# POWER_B3.net
KiCad netlist of a schematic drawn in Altium Designer
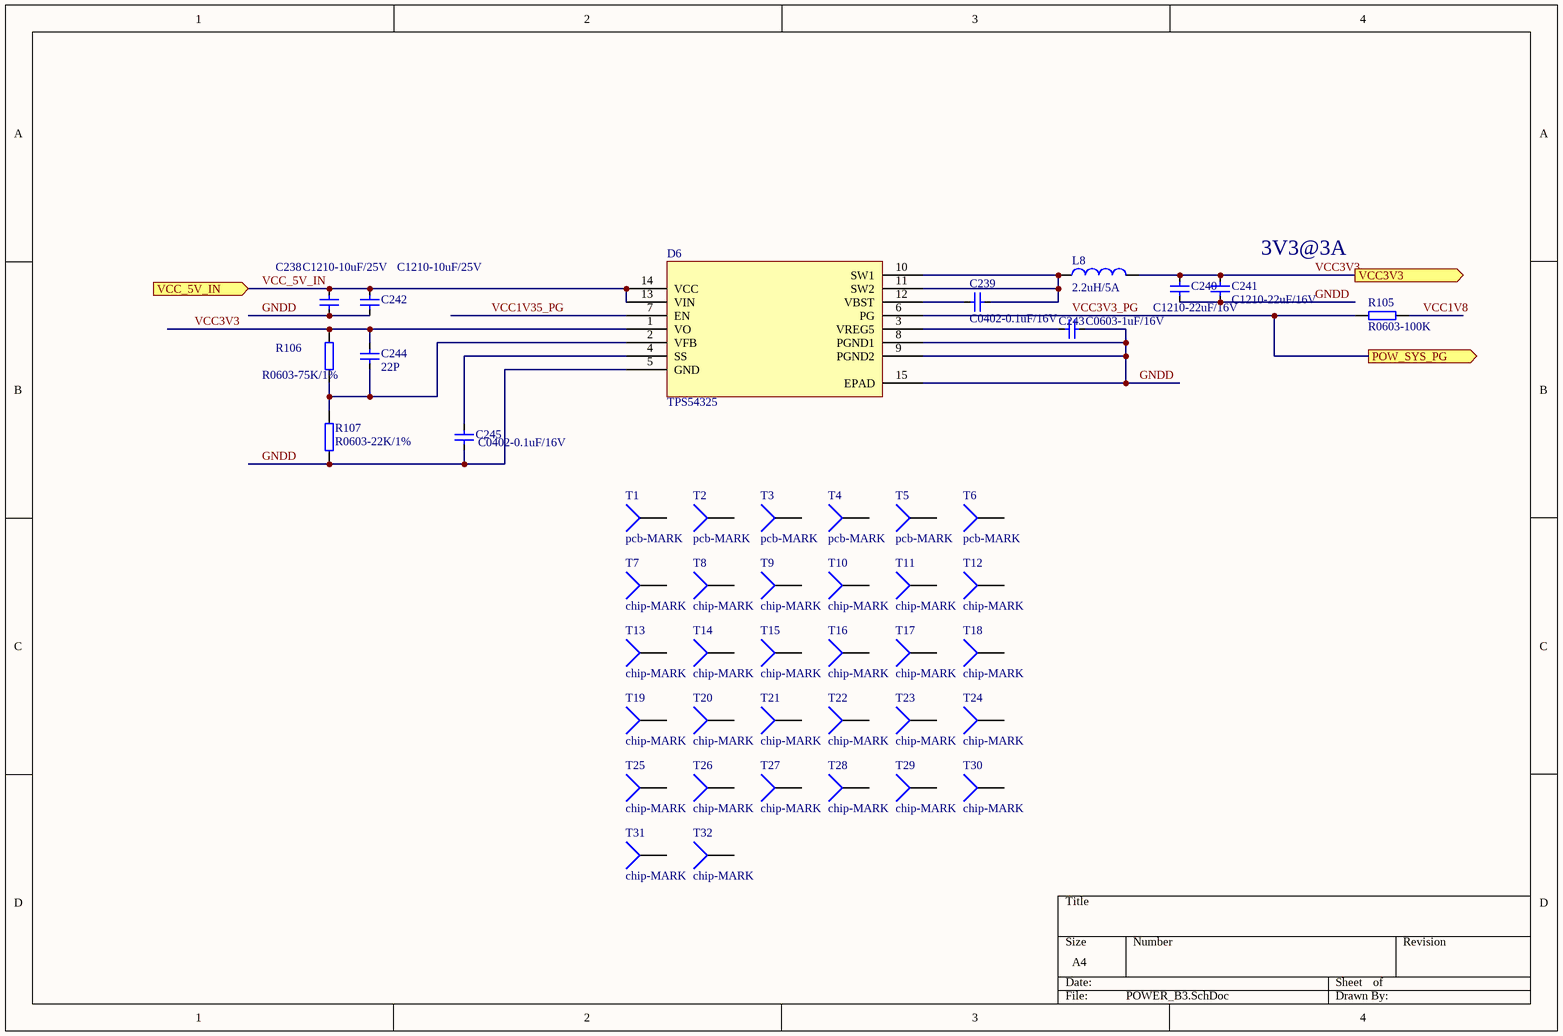
[diagram p0: POWER_B3.SchDoc]

(export (version "E")
  (design (tool "Eeschema 10.0.6"))
  (components
    (comp (ref "C238")
      (value "C1210-10uF/25V")
      (footprint "C1210")
      (fields (field (name "SCHEMATIC_PART") "CAP"))
      (libsource (lib "Database_Libs1") (part "CAP"))
    )
    (comp (ref "C239")
      (value "C0402-0.1uF/16V")
      (footprint "C0402")
      (description "X7R")
      (fields (field (name "SCHEMATIC_PART") "CAP") (field (name "MANUFACTURER") "SAMSUNG"))
      (libsource (lib "Database_Libs1") (part "CAP"))
    )
    (comp (ref "C240")
      (value "C1210-22uF/16V")
      (footprint "C1210")
      (fields (field (name "SCHEMATIC_PART") "CAP"))
      (libsource (lib "Database_Libs1") (part "CAP"))
    )
    (comp (ref "C241")
      (value "C1210-22uF/16V")
      (footprint "C1210")
      (fields (field (name "SCHEMATIC_PART") "CAP"))
      (libsource (lib "Database_Libs1") (part "CAP"))
    )
    (comp (ref "C242")
      (value "C1210-10uF/25V")
      (footprint "C1210")
      (fields (field (name "SCHEMATIC_PART") "CAP"))
      (libsource (lib "Database_Libs1") (part "CAP"))
    )
    (comp (ref "C243")
      (value "C0603-1uF/16V")
      (footprint "C0603")
      (description "X7R")
      (fields (field (name "SCHEMATIC_PART") "CAP"))
      (libsource (lib "Database_Libs1") (part "CAP"))
    )
    (comp (ref "C244")
      (value "22P")
      (footprint "C0603")
      (description "X7R")
      (fields (field (name "SCHEMATIC_PART") "CAP"))
      (libsource (lib "Database_Libs1") (part "CAP"))
    )
    (comp (ref "C245")
      (value "C0402-0.1uF/16V")
      (footprint "C0402")
      (description "X7R")
      (fields (field (name "SCHEMATIC_PART") "CAP") (field (name "MANUFACTURER") "SAMSUNG"))
      (libsource (lib "Database_Libs1") (part "CAP"))
    )
    (comp (ref "D6") (value "TPS54325") (footprint "HTSSOP-14") (libsource (lib "SCHLIB1") (part "TPS54325")))
    (comp (ref "L8")
      (value "2.2uH/5A")
      (footprint "LSMD12-13X13")
      (fields (field (name "SCHEMATIC_PART") "INDUCTOR"))
      (libsource (lib "Database_Libs1") (part "INDUCTOR"))
    )
    (comp (ref "R105")
      (value "R0603-100K")
      (footprint "R0603")
      (fields (field (name "SCHEMATIC_PART") "RES") (field (name "MANUFACTURER") "HKT"))
      (libsource (lib "Database_Libs1") (part "RES"))
    )
    (comp (ref "R106")
      (value "R0603-75K/1%")
      (footprint "R0603")
      (fields (field (name "SCHEMATIC_PART") "RES") (field (name "MANUFACTURER") "HKT"))
      (libsource (lib "Database_Libs1") (part "RES"))
    )
    (comp (ref "R107")
      (value "R0603-22K/1%")
      (footprint "R0603")
      (fields (field (name "SCHEMATIC_PART") "RES") (field (name "MANUFACTURER") "HKT"))
      (libsource (lib "Database_Libs1") (part "RES"))
    )
    (comp (ref "T1")
      (value "pcb-MARK")
      (footprint "pcb-MARK")
      (description "PCB标示 MARK点")
      (libsource (lib "Database_Libs1") (part "pcb-MARK"))
    )
    (comp (ref "T2")
      (value "pcb-MARK")
      (footprint "pcb-MARK")
      (description "PCB标示 MARK点")
      (libsource (lib "Database_Libs1") (part "pcb-MARK"))
    )
    (comp (ref "T3")
      (value "pcb-MARK")
      (footprint "pcb-MARK")
      (description "PCB标示 MARK点")
      (libsource (lib "Database_Libs1") (part "pcb-MARK"))
    )
    (comp (ref "T4")
      (value "pcb-MARK")
      (footprint "pcb-MARK")
      (description "PCB标示 MARK点")
      (libsource (lib "Database_Libs1") (part "pcb-MARK"))
    )
    (comp (ref "T5")
      (value "pcb-MARK")
      (footprint "pcb-MARK")
      (description "PCB标示 MARK点")
      (libsource (lib "Database_Libs1") (part "pcb-MARK"))
    )
    (comp (ref "T6")
      (value "pcb-MARK")
      (footprint "pcb-MARK")
      (description "PCB标示 MARK点")
      (libsource (lib "Database_Libs1") (part "pcb-MARK"))
    )
    (comp (ref "T7")
      (value "chip-MARK")
      (footprint "chip-MARK")
      (description "芯片标示 MARK点")
      (libsource (lib "Database_Libs1") (part "chip-MARK"))
    )
    (comp (ref "T8")
      (value "chip-MARK")
      (footprint "chip-MARK")
      (description "芯片标示 MARK点")
      (libsource (lib "Database_Libs1") (part "chip-MARK"))
    )
    (comp (ref "T9")
      (value "chip-MARK")
      (footprint "chip-MARK")
      (description "芯片标示 MARK点")
      (libsource (lib "Database_Libs1") (part "chip-MARK"))
    )
    (comp (ref "T10")
      (value "chip-MARK")
      (footprint "chip-MARK")
      (description "芯片标示 MARK点")
      (libsource (lib "Database_Libs1") (part "chip-MARK"))
    )
    (comp (ref "T11")
      (value "chip-MARK")
      (footprint "chip-MARK")
      (description "芯片标示 MARK点")
      (libsource (lib "Database_Libs1") (part "chip-MARK"))
    )
    (comp (ref "T12")
      (value "chip-MARK")
      (footprint "chip-MARK")
      (description "芯片标示 MARK点")
      (libsource (lib "Database_Libs1") (part "chip-MARK"))
    )
    (comp (ref "T13")
      (value "chip-MARK")
      (footprint "chip-MARK")
      (description "芯片标示 MARK点")
      (libsource (lib "Database_Libs1") (part "chip-MARK"))
    )
    (comp (ref "T14")
      (value "chip-MARK")
      (footprint "chip-MARK")
      (description "芯片标示 MARK点")
      (libsource (lib "Database_Libs1") (part "chip-MARK"))
    )
    (comp (ref "T15")
      (value "chip-MARK")
      (footprint "chip-MARK")
      (description "芯片标示 MARK点")
      (libsource (lib "Database_Libs1") (part "chip-MARK"))
    )
    (comp (ref "T16")
      (value "chip-MARK")
      (footprint "chip-MARK")
      (description "芯片标示 MARK点")
      (libsource (lib "Database_Libs1") (part "chip-MARK"))
    )
    (comp (ref "T17")
      (value "chip-MARK")
      (footprint "chip-MARK")
      (description "芯片标示 MARK点")
      (libsource (lib "Database_Libs1") (part "chip-MARK"))
    )
    (comp (ref "T18")
      (value "chip-MARK")
      (footprint "chip-MARK")
      (description "芯片标示 MARK点")
      (libsource (lib "Database_Libs1") (part "chip-MARK"))
    )
    (comp (ref "T19")
      (value "chip-MARK")
      (footprint "chip-MARK")
      (description "芯片标示 MARK点")
      (libsource (lib "Database_Libs1") (part "chip-MARK"))
    )
    (comp (ref "T20")
      (value "chip-MARK")
      (footprint "chip-MARK")
      (description "芯片标示 MARK点")
      (libsource (lib "Database_Libs1") (part "chip-MARK"))
    )
    (comp (ref "T21")
      (value "chip-MARK")
      (footprint "chip-MARK")
      (description "芯片标示 MARK点")
      (libsource (lib "Database_Libs1") (part "chip-MARK"))
    )
    (comp (ref "T22")
      (value "chip-MARK")
      (footprint "chip-MARK")
      (description "芯片标示 MARK点")
      (libsource (lib "Database_Libs1") (part "chip-MARK"))
    )
    (comp (ref "T23")
      (value "chip-MARK")
      (footprint "chip-MARK")
      (description "芯片标示 MARK点")
      (libsource (lib "Database_Libs1") (part "chip-MARK"))
    )
    (comp (ref "T24")
      (value "chip-MARK")
      (footprint "chip-MARK")
      (description "芯片标示 MARK点")
      (libsource (lib "Database_Libs1") (part "chip-MARK"))
    )
    (comp (ref "T25")
      (value "chip-MARK")
      (footprint "chip-MARK")
      (description "芯片标示 MARK点")
      (libsource (lib "Database_Libs1") (part "chip-MARK"))
    )
    (comp (ref "T26")
      (value "chip-MARK")
      (footprint "chip-MARK")
      (description "芯片标示 MARK点")
      (libsource (lib "Database_Libs1") (part "chip-MARK"))
    )
    (comp (ref "T27")
      (value "chip-MARK")
      (footprint "chip-MARK")
      (description "芯片标示 MARK点")
      (libsource (lib "Database_Libs1") (part "chip-MARK"))
    )
    (comp (ref "T28")
      (value "chip-MARK")
      (footprint "chip-MARK")
      (description "芯片标示 MARK点")
      (libsource (lib "Database_Libs1") (part "chip-MARK"))
    )
    (comp (ref "T29")
      (value "chip-MARK")
      (footprint "chip-MARK")
      (description "芯片标示 MARK点")
      (libsource (lib "Database_Libs1") (part "chip-MARK"))
    )
    (comp (ref "T30")
      (value "chip-MARK")
      (footprint "chip-MARK")
      (description "芯片标示 MARK点")
      (libsource (lib "Database_Libs1") (part "chip-MARK"))
    )
    (comp (ref "T31")
      (value "chip-MARK")
      (footprint "chip-MARK")
      (description "芯片标示 MARK点")
      (libsource (lib "Database_Libs1") (part "chip-MARK"))
    )
    (comp (ref "T32")
      (value "chip-MARK")
      (footprint "chip-MARK")
      (description "芯片标示 MARK点")
      (libsource (lib "Database_Libs1") (part "chip-MARK"))
    )
  )
  (nets
    (net (code "1") (name "/GNDD") (class "Default")
      (node (ref "C238") (pin "2") (pinfunction "2_2") (pintype "passive"))
      (node (ref "C240") (pin "2") (pinfunction "2_2") (pintype "passive"))
      (node (ref "C241") (pin "2") (pinfunction "2_2") (pintype "passive"))
      (node (ref "C242") (pin "2") (pinfunction "2_2") (pintype "passive"))
      (node (ref "C243") (pin "2") (pinfunction "2_2") (pintype "passive"))
      (node (ref "C245") (pin "2") (pinfunction "2_2") (pintype "passive"))
      (node (ref "D6") (pin "15") (pinfunction "EPAD_15") (pintype "passive"))
      (node (ref "D6") (pin "5") (pinfunction "GND_5") (pintype "passive"))
      (node (ref "D6") (pin "8") (pinfunction "PGND1_8") (pintype "passive"))
      (node (ref "D6") (pin "9") (pinfunction "PGND2_9") (pintype "passive"))
      (node (ref "R107") (pin "1") (pintype "passive"))
    )
    (net (code "2") (name "/VCC1V8") (class "Default") (node (ref "R105") (pin "2") (pintype "passive")))
    (net (code "3") (name "/VCC1V35_PG") (class "Default")
      (node (ref "D6") (pin "7") (pinfunction "EN_7") (pintype "passive"))
    )
    (net (code "4") (name "/VCC3V3") (class "Default")
      (node (ref "C240") (pin "1") (pinfunction "1_1") (pintype "passive"))
      (node (ref "C241") (pin "1") (pinfunction "1_1") (pintype "passive"))
      (node (ref "C244") (pin "1") (pinfunction "1_1") (pintype "passive"))
      (node (ref "D6") (pin "1") (pinfunction "VO_1") (pintype "passive"))
      (node (ref "L8") (pin "2") (pinfunction "2_2") (pintype "passive"))
      (node (ref "R106") (pin "2") (pintype "passive"))
    )
    (net (code "5") (name "/VCC3V3_PG") (class "Default")
      (node (ref "D6") (pin "6") (pinfunction "PG_6") (pintype "passive"))
      (node (ref "R105") (pin "1") (pintype "passive"))
    )
    (net (code "6") (name "/VCC_5V_IN") (class "Default")
      (node (ref "C238") (pin "1") (pinfunction "1_1") (pintype "passive"))
      (node (ref "C242") (pin "1") (pinfunction "1_1") (pintype "passive"))
      (node (ref "D6") (pin "13") (pinfunction "VIN_13") (pintype "passive"))
      (node (ref "D6") (pin "14") (pinfunction "VCC_14") (pintype "passive"))
    )
    (net (code "7") (name "Net-(D6-SS)") (class "Default")
      (node (ref "C245") (pin "1") (pinfunction "1_1") (pintype "passive"))
      (node (ref "D6") (pin "4") (pinfunction "SS_4") (pintype "passive"))
    )
    (net (code "8") (name "Net-(D6-SW1)") (class "Default")
      (node (ref "C239") (pin "2") (pinfunction "2_2") (pintype "passive"))
      (node (ref "D6") (pin "10") (pinfunction "SW1_10") (pintype "passive"))
      (node (ref "D6") (pin "11") (pinfunction "SW2_11") (pintype "passive"))
      (node (ref "L8") (pin "1") (pinfunction "1_1") (pintype "passive"))
    )
    (net (code "9") (name "Net-(D6-VBST)") (class "Default")
      (node (ref "C239") (pin "1") (pinfunction "1_1") (pintype "passive"))
      (node (ref "D6") (pin "12") (pinfunction "VBST_12") (pintype "passive"))
    )
    (net (code "10") (name "Net-(D6-VFB)") (class "Default")
      (node (ref "C244") (pin "2") (pinfunction "2_2") (pintype "passive"))
      (node (ref "D6") (pin "2") (pinfunction "VFB_2") (pintype "passive"))
      (node (ref "R106") (pin "1") (pintype "passive"))
      (node (ref "R107") (pin "2") (pintype "passive"))
    )
    (net (code "11") (name "Net-(D6-VREG5)") (class "Default")
      (node (ref "C243") (pin "1") (pinfunction "1_1") (pintype "passive"))
      (node (ref "D6") (pin "3") (pinfunction "VREG5_3") (pintype "passive"))
    )
    (net (code "12") (name "unconnected-(T1-Pad1)") (class "Default")
      (node (ref "T1") (pin "1") (pinfunction "1_1") (pintype "passive"))
    )
    (net (code "13") (name "unconnected-(T2-Pad1)") (class "Default")
      (node (ref "T2") (pin "1") (pinfunction "1_1") (pintype "passive"))
    )
    (net (code "14") (name "unconnected-(T3-Pad1)") (class "Default")
      (node (ref "T3") (pin "1") (pinfunction "1_1") (pintype "passive"))
    )
    (net (code "15") (name "unconnected-(T4-Pad1)") (class "Default")
      (node (ref "T4") (pin "1") (pinfunction "1_1") (pintype "passive"))
    )
    (net (code "16") (name "unconnected-(T5-Pad1)") (class "Default")
      (node (ref "T5") (pin "1") (pinfunction "1_1") (pintype "passive"))
    )
    (net (code "17") (name "unconnected-(T6-Pad1)") (class "Default")
      (node (ref "T6") (pin "1") (pinfunction "1_1") (pintype "passive"))
    )
    (net (code "18") (name "unconnected-(T7-Pad1)") (class "Default")
      (node (ref "T7") (pin "1") (pinfunction "1_1") (pintype "passive"))
    )
    (net (code "19") (name "unconnected-(T8-Pad1)") (class "Default")
      (node (ref "T8") (pin "1") (pinfunction "1_1") (pintype "passive"))
    )
    (net (code "20") (name "unconnected-(T9-Pad1)") (class "Default")
      (node (ref "T9") (pin "1") (pinfunction "1_1") (pintype "passive"))
    )
    (net (code "21") (name "unconnected-(T10-Pad1)") (class "Default")
      (node (ref "T10") (pin "1") (pinfunction "1_1") (pintype "passive"))
    )
    (net (code "22") (name "unconnected-(T11-Pad1)") (class "Default")
      (node (ref "T11") (pin "1") (pinfunction "1_1") (pintype "passive"))
    )
    (net (code "23") (name "unconnected-(T12-Pad1)") (class "Default")
      (node (ref "T12") (pin "1") (pinfunction "1_1") (pintype "passive"))
    )
    (net (code "24") (name "unconnected-(T13-Pad1)") (class "Default")
      (node (ref "T13") (pin "1") (pinfunction "1_1") (pintype "passive"))
    )
    (net (code "25") (name "unconnected-(T14-Pad1)") (class "Default")
      (node (ref "T14") (pin "1") (pinfunction "1_1") (pintype "passive"))
    )
    (net (code "26") (name "unconnected-(T15-Pad1)") (class "Default")
      (node (ref "T15") (pin "1") (pinfunction "1_1") (pintype "passive"))
    )
    (net (code "27") (name "unconnected-(T16-Pad1)") (class "Default")
      (node (ref "T16") (pin "1") (pinfunction "1_1") (pintype "passive"))
    )
    (net (code "28") (name "unconnected-(T17-Pad1)") (class "Default")
      (node (ref "T17") (pin "1") (pinfunction "1_1") (pintype "passive"))
    )
    (net (code "29") (name "unconnected-(T18-Pad1)") (class "Default")
      (node (ref "T18") (pin "1") (pinfunction "1_1") (pintype "passive"))
    )
    (net (code "30") (name "unconnected-(T19-Pad1)") (class "Default")
      (node (ref "T19") (pin "1") (pinfunction "1_1") (pintype "passive"))
    )
    (net (code "31") (name "unconnected-(T20-Pad1)") (class "Default")
      (node (ref "T20") (pin "1") (pinfunction "1_1") (pintype "passive"))
    )
    (net (code "32") (name "unconnected-(T21-Pad1)") (class "Default")
      (node (ref "T21") (pin "1") (pinfunction "1_1") (pintype "passive"))
    )
    (net (code "33") (name "unconnected-(T22-Pad1)") (class "Default")
      (node (ref "T22") (pin "1") (pinfunction "1_1") (pintype "passive"))
    )
    (net (code "34") (name "unconnected-(T23-Pad1)") (class "Default")
      (node (ref "T23") (pin "1") (pinfunction "1_1") (pintype "passive"))
    )
    (net (code "35") (name "unconnected-(T24-Pad1)") (class "Default")
      (node (ref "T24") (pin "1") (pinfunction "1_1") (pintype "passive"))
    )
    (net (code "36") (name "unconnected-(T25-Pad1)") (class "Default")
      (node (ref "T25") (pin "1") (pinfunction "1_1") (pintype "passive"))
    )
    (net (code "37") (name "unconnected-(T26-Pad1)") (class "Default")
      (node (ref "T26") (pin "1") (pinfunction "1_1") (pintype "passive"))
    )
    (net (code "38") (name "unconnected-(T27-Pad1)") (class "Default")
      (node (ref "T27") (pin "1") (pinfunction "1_1") (pintype "passive"))
    )
    (net (code "39") (name "unconnected-(T28-Pad1)") (class "Default")
      (node (ref "T28") (pin "1") (pinfunction "1_1") (pintype "passive"))
    )
    (net (code "40") (name "unconnected-(T29-Pad1)") (class "Default")
      (node (ref "T29") (pin "1") (pinfunction "1_1") (pintype "passive"))
    )
    (net (code "41") (name "unconnected-(T30-Pad1)") (class "Default")
      (node (ref "T30") (pin "1") (pinfunction "1_1") (pintype "passive"))
    )
    (net (code "42") (name "unconnected-(T31-Pad1)") (class "Default")
      (node (ref "T31") (pin "1") (pinfunction "1_1") (pintype "passive"))
    )
    (net (code "43") (name "unconnected-(T32-Pad1)") (class "Default")
      (node (ref "T32") (pin "1") (pinfunction "1_1") (pintype "passive"))
    )
  )
)
